# kitcop4.net
KiCad netlist of a schematic drawn in EAGLE
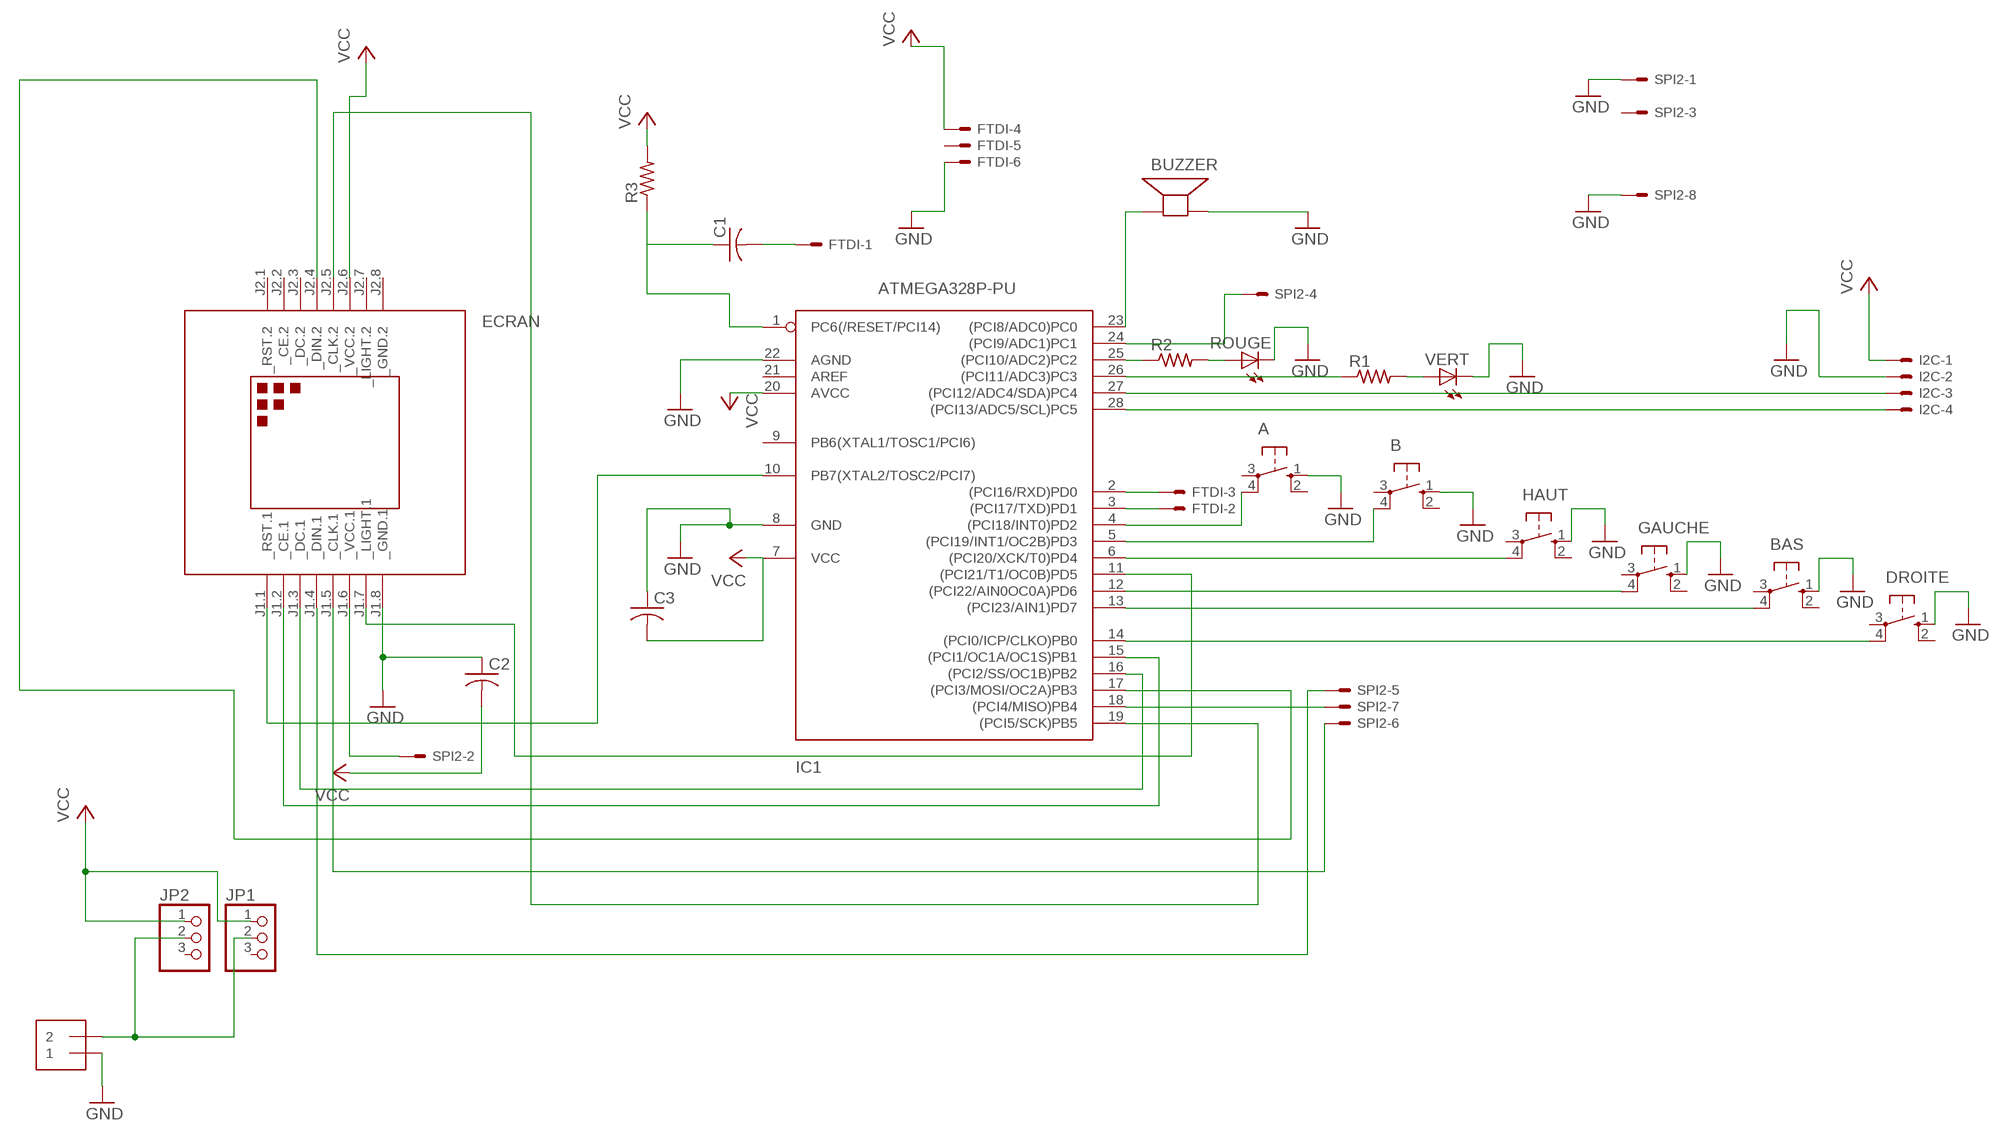
[diagram p0: schematic, sheet 1]

(export (version "E")
  (design (tool "Eeschema 10.0.6"))
  (components
    (comp (ref "A")
      (value "10-XX")
      (footprint "eagle-import:B3F-10XX")
      (fields (field (name "MPN") "B3F-1000"))
      (libsource (lib "eagle-import") (part "10-XX"))
    )
    (comp (ref "B")
      (value "10-XX")
      (footprint "eagle-import:B3F-10XX")
      (fields (field (name "MPN") "B3F-1000"))
      (libsource (lib "eagle-import") (part "10-XX"))
    )
    (comp (ref "BAS")
      (value "10-XX")
      (footprint "eagle-import:B3F-10XX")
      (fields (field (name "MPN") "B3F-1000"))
      (libsource (lib "eagle-import") (part "10-XX"))
    )
    (comp (ref "BUZZER")
      (value "SPEAKER/AL60P")
      (footprint "eagle-import:AL60P")
      (libsource (lib "eagle-import") (part "SPEAKER/AL60P"))
    )
    (comp (ref "C1")
      (value "C-US025-040X050")
      (footprint "eagle-import:C025-040X050")
      (libsource (lib "eagle-import") (part "C-US025-040X050"))
    )
    (comp (ref "C2")
      (value "C-US025-040X050")
      (footprint "eagle-import:C025-040X050")
      (libsource (lib "eagle-import") (part "C-US025-040X050"))
    )
    (comp (ref "C3")
      (value "C-US025-040X050")
      (footprint "eagle-import:C025-040X050")
      (libsource (lib "eagle-import") (part "C-US025-040X050"))
    )
    (comp (ref "DROITE")
      (value "10-XX")
      (footprint "eagle-import:B3F-10XX")
      (fields (field (name "MPN") "B3F-1000"))
      (libsource (lib "eagle-import") (part "10-XX"))
    )
    (comp (ref "ECRAN")
      (value "DISPLAY-NOKIA-3310")
      (footprint "eagle-import:DISPLAY-NOKIA-3310")
      (libsource (lib "eagle-import") (part "DISPLAY-NOKIA-3310"))
    )
    (comp (ref "FTDI")
      (value "22-23-2061")
      (footprint "eagle-import:22-23-2061")
      (fields (field (name "MF") "MOLEX"))
      (libsource (lib "eagle-import") (part "22-23-2061"))
    )
    (comp (ref "GAUCHE")
      (value "10-XX")
      (footprint "eagle-import:B3F-10XX")
      (fields (field (name "MPN") "B3F-1000"))
      (libsource (lib "eagle-import") (part "10-XX"))
    )
    (comp (ref "HAUT")
      (value "10-XX")
      (footprint "eagle-import:B3F-10XX")
      (fields (field (name "MPN") "B3F-1000"))
      (libsource (lib "eagle-import") (part "10-XX"))
    )
    (comp (ref "I2C")
      (value "22-23-2041")
      (footprint "eagle-import:22-23-2041")
      (fields (field (name "MF") "MOLEX"))
      (libsource (lib "eagle-import") (part "22-23-2041"))
    )
    (comp (ref "IC1")
      (value "ATMEGA328P-PU")
      (footprint "eagle-import:DIL28-3")
      (libsource (lib "eagle-import") (part "ATMEGA168PV-10"))
    )
    (comp (ref "J1")
      (value "1X2-3.5MM")
      (footprint "eagle-import:1X2-3.5MM")
      (libsource (lib "eagle-import") (part "1X2-3.5MM"))
    )
    (comp (ref "JP1")
      (value "PINHD-1X3")
      (footprint "eagle-import:1X03")
      (libsource (lib "eagle-import") (part "PINHD-1X3"))
    )
    (comp (ref "JP2")
      (value "PINHD-1X3")
      (footprint "eagle-import:1X03")
      (libsource (lib "eagle-import") (part "PINHD-1X3"))
    )
    (comp (ref "R1")
      (value "R-US_0207/10")
      (footprint "eagle-import:0207_10")
      (libsource (lib "eagle-import") (part "R-US_0207/10"))
    )
    (comp (ref "R2")
      (value "R-US_0207/10")
      (footprint "eagle-import:0207_10")
      (libsource (lib "eagle-import") (part "R-US_0207/10"))
    )
    (comp (ref "R3")
      (value "R-US_0207/10")
      (footprint "eagle-import:0207_10")
      (libsource (lib "eagle-import") (part "R-US_0207/10"))
    )
    (comp (ref "ROUGE")
      (value "LED5MM")
      (footprint "eagle-import:LED5MM")
      (libsource (lib "eagle-import") (part "LED5MM"))
    )
    (comp (ref "SPI2")
      (value "22-23-2081")
      (footprint "eagle-import:22-23-2081")
      (fields (field (name "MF") "MOLEX"))
      (libsource (lib "eagle-import") (part "22-23-2081"))
    )
    (comp (ref "VERT")
      (value "LED5MM")
      (footprint "eagle-import:LED5MM")
      (libsource (lib "eagle-import") (part "LED5MM"))
    )
  )
  (nets
    (net (code "1") (name "/_CE.2") (class "Default")
      (node (ref "ECRAN") (pin "J2.2") (pinfunction "_CE.2_J2.2") (pintype "power_in"))
    )
    (net (code "2") (name "/_RST.2") (class "Default")
      (node (ref "ECRAN") (pin "J2.1") (pinfunction "_RST.2_J2.1") (pintype "power_in"))
    )
    (net (code "3") (name "GND") (class "Default")
      (node (ref "A") (pin "1") (pinfunction "S_1") (pintype "passive"))
      (node (ref "B") (pin "1") (pinfunction "S_1") (pintype "passive"))
      (node (ref "BAS") (pin "1") (pinfunction "S_1") (pintype "passive"))
      (node (ref "BUZZER") (pin "2") (pinfunction "-_2") (pintype "passive"))
      (node (ref "C2") (pin "1") (pinfunction "1_1") (pintype "passive"))
      (node (ref "C3") (pin "1") (pinfunction "1_1") (pintype "passive"))
      (node (ref "DROITE") (pin "1") (pinfunction "S_1") (pintype "passive"))
      (node (ref "ECRAN") (pin "J1.8") (pinfunction "_GND.1_J1.8") (pintype "input"))
      (node (ref "FTDI") (pin "6") (pinfunction "S_6") (pintype "passive"))
      (node (ref "GAUCHE") (pin "1") (pinfunction "S_1") (pintype "passive"))
      (node (ref "HAUT") (pin "1") (pinfunction "S_1") (pintype "passive"))
      (node (ref "I2C") (pin "2") (pinfunction "S_2") (pintype "passive"))
      (node (ref "IC1") (pin "22") (pinfunction "AGND_22") (pintype "bidirectional"))
      (node (ref "IC1") (pin "8") (pinfunction "GND_8") (pintype "bidirectional"))
      (node (ref "J1") (pin "1") (pinfunction "1_1") (pintype "passive"))
      (node (ref "ROUGE") (pin "K") (pinfunction "C_K") (pintype "passive"))
      (node (ref "SPI2") (pin "1") (pinfunction "S_1") (pintype "passive"))
      (node (ref "SPI2") (pin "8") (pinfunction "S_8") (pintype "passive"))
      (node (ref "VERT") (pin "K") (pinfunction "C_K") (pintype "passive"))
    )
    (net (code "4") (name "Net-(A-P1)") (class "Default")
      (node (ref "A") (pin "4") (pinfunction "P1_4") (pintype "passive"))
      (node (ref "IC1") (pin "4") (pinfunction "(PCI18/INT0)PD2_4") (pintype "bidirectional"))
    )
    (net (code "5") (name "Net-(B-P1)") (class "Default")
      (node (ref "B") (pin "4") (pinfunction "P1_4") (pintype "passive"))
      (node (ref "IC1") (pin "5") (pinfunction "(PCI19/INT1/OC2B)PD3_5") (pintype "bidirectional"))
    )
    (net (code "6") (name "Net-(BAS-P1)") (class "Default")
      (node (ref "BAS") (pin "4") (pinfunction "P1_4") (pintype "passive"))
      (node (ref "IC1") (pin "13") (pinfunction "(PCI23/AIN1)PD7_13") (pintype "bidirectional"))
    )
    (net (code "7") (name "Net-(BUZZER-+)") (class "Default")
      (node (ref "BUZZER") (pin "1") (pinfunction "+_1") (pintype "passive"))
      (node (ref "IC1") (pin "23") (pinfunction "(PCI8/ADC0)PC0_23") (pintype "bidirectional"))
    )
    (net (code "8") (name "Net-(DROITE-P1)") (class "Default")
      (node (ref "DROITE") (pin "4") (pinfunction "P1_4") (pintype "passive"))
      (node (ref "IC1") (pin "14") (pinfunction "(PCI0/ICP/CLKO)PB0_14") (pintype "bidirectional"))
    )
    (net (code "9") (name "Net-(ECRAN-_CE.1)") (class "Default")
      (node (ref "ECRAN") (pin "J1.2") (pinfunction "_CE.1_J1.2") (pintype "power_in"))
      (node (ref "IC1") (pin "15") (pinfunction "(PCI1/OC1A/OC1S)PB1_15") (pintype "bidirectional"))
    )
    (net (code "10") (name "Net-(ECRAN-_CLK.1)") (class "Default")
      (node (ref "ECRAN") (pin "J1.5") (pinfunction "_CLK.1_J1.5") (pintype "bidirectional"))
      (node (ref "SPI2") (pin "6") (pinfunction "S_6") (pintype "passive"))
    )
    (net (code "11") (name "Net-(ECRAN-_CLK.2)") (class "Default")
      (node (ref "ECRAN") (pin "J2.5") (pinfunction "_CLK.2_J2.5") (pintype "bidirectional"))
      (node (ref "IC1") (pin "19") (pinfunction "(PCI5/SCK)PB5_19") (pintype "bidirectional"))
    )
    (net (code "12") (name "Net-(ECRAN-_DC.1)") (class "Default")
      (node (ref "ECRAN") (pin "J1.3") (pinfunction "_DC.1_J1.3") (pintype "bidirectional"))
      (node (ref "IC1") (pin "16") (pinfunction "(PCI2/SS/OC1B)PB2_16") (pintype "bidirectional"))
    )
    (net (code "13") (name "Net-(ECRAN-_DIN.1)") (class "Default")
      (node (ref "ECRAN") (pin "J1.4") (pinfunction "_DIN.1_J1.4") (pintype "bidirectional"))
      (node (ref "SPI2") (pin "5") (pinfunction "S_5") (pintype "passive"))
    )
    (net (code "14") (name "Net-(ECRAN-_DIN.2)") (class "Default")
      (node (ref "ECRAN") (pin "J2.4") (pinfunction "_DIN.2_J2.4") (pintype "bidirectional"))
      (node (ref "IC1") (pin "17") (pinfunction "(PCI3/MOSI/OC2A)PB3_17") (pintype "bidirectional"))
    )
    (net (code "15") (name "Net-(ECRAN-_LIGHT.1)") (class "Default")
      (node (ref "ECRAN") (pin "J1.7") (pinfunction "_LIGHT.1_J1.7") (pintype "bidirectional"))
      (node (ref "IC1") (pin "11") (pinfunction "(PCI21/T1/OC0B)PD5_11") (pintype "bidirectional"))
    )
    (net (code "16") (name "Net-(ECRAN-_RST.1)") (class "Default")
      (node (ref "ECRAN") (pin "J1.1") (pinfunction "_RST.1_J1.1") (pintype "power_in"))
      (node (ref "IC1") (pin "10") (pinfunction "PB7(XTAL2/TOSC2/PCI7)_10") (pintype "bidirectional"))
    )
    (net (code "17") (name "Net-(ECRAN-_VCC.1)") (class "Default")
      (node (ref "ECRAN") (pin "J1.6") (pinfunction "_VCC.1_J1.6") (pintype "bidirectional"))
      (node (ref "SPI2") (pin "2") (pinfunction "S_2") (pintype "passive"))
    )
    (net (code "18") (name "Net-(FTDIA-S)") (class "Default")
      (node (ref "C1") (pin "2") (pinfunction "2_2") (pintype "passive"))
      (node (ref "FTDI") (pin "1") (pinfunction "S_1") (pintype "passive"))
    )
    (net (code "19") (name "Net-(FTDIB-S)") (class "Default")
      (node (ref "FTDI") (pin "2") (pinfunction "S_2") (pintype "passive"))
      (node (ref "IC1") (pin "3") (pinfunction "(PCI17/TXD)PD1_3") (pintype "bidirectional"))
    )
    (net (code "20") (name "Net-(FTDIC-S)") (class "Default")
      (node (ref "FTDI") (pin "3") (pinfunction "S_3") (pintype "passive"))
      (node (ref "IC1") (pin "2") (pinfunction "(PCI16/RXD)PD0_2") (pintype "bidirectional"))
    )
    (net (code "21") (name "Net-(GAUCHE-P1)") (class "Default")
      (node (ref "GAUCHE") (pin "4") (pinfunction "P1_4") (pintype "passive"))
      (node (ref "IC1") (pin "12") (pinfunction "(PCI22/AIN0OC0A)PD6_12") (pintype "bidirectional"))
    )
    (net (code "22") (name "Net-(HAUT-P1)") (class "Default")
      (node (ref "HAUT") (pin "4") (pinfunction "P1_4") (pintype "passive"))
      (node (ref "IC1") (pin "6") (pinfunction "(PCI20/XCK/T0)PD4_6") (pintype "bidirectional"))
    )
    (net (code "23") (name "Net-(I2CC-S)") (class "Default")
      (node (ref "I2C") (pin "3") (pinfunction "S_3") (pintype "passive"))
      (node (ref "IC1") (pin "27") (pinfunction "(PCI12/ADC4/SDA)PC4_27") (pintype "bidirectional"))
    )
    (net (code "24") (name "Net-(I2CD-S)") (class "Default")
      (node (ref "I2C") (pin "4") (pinfunction "S_4") (pintype "passive"))
      (node (ref "IC1") (pin "28") (pinfunction "(PCI13/ADC5/SCL)PC5_28") (pintype "bidirectional"))
    )
    (net (code "25") (name "Net-(IC1-(PCI4{slash}MISO)PB4)") (class "Default")
      (node (ref "IC1") (pin "18") (pinfunction "(PCI4/MISO)PB4_18") (pintype "bidirectional"))
      (node (ref "SPI2") (pin "7") (pinfunction "S_7") (pintype "passive"))
    )
    (net (code "26") (name "Net-(IC1-(PCI9{slash}ADC1)PC1)") (class "Default")
      (node (ref "IC1") (pin "24") (pinfunction "(PCI9/ADC1)PC1_24") (pintype "bidirectional"))
      (node (ref "SPI2") (pin "4") (pinfunction "S_4") (pintype "passive"))
    )
    (net (code "27") (name "Net-(IC1-(PCI10{slash}ADC2)PC2)") (class "Default")
      (node (ref "IC1") (pin "25") (pinfunction "(PCI10/ADC2)PC2_25") (pintype "bidirectional"))
      (node (ref "R2") (pin "1") (pinfunction "1_1") (pintype "passive"))
    )
    (net (code "28") (name "Net-(IC1-(PCI11{slash}ADC3)PC3)") (class "Default")
      (node (ref "IC1") (pin "26") (pinfunction "(PCI11/ADC3)PC3_26") (pintype "bidirectional"))
      (node (ref "R1") (pin "1") (pinfunction "1_1") (pintype "passive"))
    )
    (net (code "29") (name "Net-(IC1-PC6({slash}RESET{slash}PCI14))") (class "Default")
      (node (ref "C1") (pin "1") (pinfunction "1_1") (pintype "passive"))
      (node (ref "IC1") (pin "1") (pinfunction "PC6(/RESET/PCI14)_1") (pintype "bidirectional"))
      (node (ref "R3") (pin "1") (pinfunction "1_1") (pintype "passive"))
    )
    (net (code "30") (name "Net-(J1-Pad2)") (class "Default")
      (node (ref "J1") (pin "2") (pinfunction "2_2") (pintype "passive"))
      (node (ref "JP1") (pin "2") (pinfunction "2_2") (pintype "passive"))
      (node (ref "JP2") (pin "2") (pinfunction "2_2") (pintype "passive"))
    )
    (net (code "31") (name "Net-(R1-Pad2)") (class "Default")
      (node (ref "R1") (pin "2") (pinfunction "2_2") (pintype "passive"))
      (node (ref "VERT") (pin "A") (pinfunction "A_A") (pintype "passive"))
    )
    (net (code "32") (name "Net-(R2-Pad2)") (class "Default")
      (node (ref "R2") (pin "2") (pinfunction "2_2") (pintype "passive"))
      (node (ref "ROUGE") (pin "A") (pinfunction "A_A") (pintype "passive"))
    )
    (net (code "33") (name "VCC") (class "Default")
      (node (ref "C2") (pin "2") (pinfunction "2_2") (pintype "passive"))
      (node (ref "C3") (pin "2") (pinfunction "2_2") (pintype "passive"))
      (node (ref "ECRAN") (pin "J2.6") (pinfunction "_VCC.2_J2.6") (pintype "bidirectional"))
      (node (ref "FTDI") (pin "4") (pinfunction "S_4") (pintype "passive"))
      (node (ref "I2C") (pin "1") (pinfunction "S_1") (pintype "passive"))
      (node (ref "IC1") (pin "20") (pinfunction "AVCC_20") (pintype "bidirectional"))
      (node (ref "IC1") (pin "7") (pinfunction "VCC_7") (pintype "bidirectional"))
      (node (ref "JP1") (pin "1") (pinfunction "1_1") (pintype "passive"))
      (node (ref "JP2") (pin "1") (pinfunction "1_1") (pintype "passive"))
      (node (ref "R3") (pin "2") (pinfunction "2_2") (pintype "passive"))
    )
    (net (code "34") (name "unconnected-(A-P-Pad3)") (class "Default")
      (node (ref "A") (pin "3") (pinfunction "P_3") (pintype "passive"))
    )
    (net (code "35") (name "unconnected-(A-S1-Pad2)") (class "Default")
      (node (ref "A") (pin "2") (pinfunction "S1_2") (pintype "passive"))
    )
    (net (code "36") (name "unconnected-(B-P-Pad3)") (class "Default")
      (node (ref "B") (pin "3") (pinfunction "P_3") (pintype "passive"))
    )
    (net (code "37") (name "unconnected-(B-S1-Pad2)") (class "Default")
      (node (ref "B") (pin "2") (pinfunction "S1_2") (pintype "passive"))
    )
    (net (code "38") (name "unconnected-(BAS-P-Pad3)") (class "Default")
      (node (ref "BAS") (pin "3") (pinfunction "P_3") (pintype "passive"))
    )
    (net (code "39") (name "unconnected-(BAS-S1-Pad2)") (class "Default")
      (node (ref "BAS") (pin "2") (pinfunction "S1_2") (pintype "passive"))
    )
    (net (code "40") (name "unconnected-(DROITE-P-Pad3)") (class "Default")
      (node (ref "DROITE") (pin "3") (pinfunction "P_3") (pintype "passive"))
    )
    (net (code "41") (name "unconnected-(DROITE-S1-Pad2)") (class "Default")
      (node (ref "DROITE") (pin "2") (pinfunction "S1_2") (pintype "passive"))
    )
    (net (code "42") (name "unconnected-(ECRAN-_DC.2-PadJ2.3)") (class "Default")
      (node (ref "ECRAN") (pin "J2.3") (pinfunction "_DC.2_J2.3") (pintype "bidirectional"))
    )
    (net (code "43") (name "unconnected-(ECRAN-_GND.2-PadJ2.8)") (class "Default")
      (node (ref "ECRAN") (pin "J2.8") (pinfunction "_GND.2_J2.8") (pintype "input"))
    )
    (net (code "44") (name "unconnected-(ECRAN-_LIGHT.2-PadJ2.7)") (class "Default")
      (node (ref "ECRAN") (pin "J2.7") (pinfunction "_LIGHT.2_J2.7") (pintype "bidirectional"))
    )
    (net (code "45") (name "unconnected-(FTDIE-S-Pad5)") (class "Default")
      (node (ref "FTDI") (pin "5") (pinfunction "S_5") (pintype "passive"))
    )
    (net (code "46") (name "unconnected-(GAUCHE-P-Pad3)") (class "Default")
      (node (ref "GAUCHE") (pin "3") (pinfunction "P_3") (pintype "passive"))
    )
    (net (code "47") (name "unconnected-(GAUCHE-S1-Pad2)") (class "Default")
      (node (ref "GAUCHE") (pin "2") (pinfunction "S1_2") (pintype "passive"))
    )
    (net (code "48") (name "unconnected-(HAUT-P-Pad3)") (class "Default")
      (node (ref "HAUT") (pin "3") (pinfunction "P_3") (pintype "passive"))
    )
    (net (code "49") (name "unconnected-(HAUT-S1-Pad2)") (class "Default")
      (node (ref "HAUT") (pin "2") (pinfunction "S1_2") (pintype "passive"))
    )
    (net (code "50") (name "unconnected-(IC1-AREF-Pad21)") (class "Default")
      (node (ref "IC1") (pin "21") (pinfunction "AREF_21") (pintype "bidirectional"))
    )
    (net (code "51") (name "unconnected-(IC1-PB6(XTAL1{slash}TOSC1{slash}PCI6)-Pad9)") (class "Default")
      (node (ref "IC1") (pin "9") (pinfunction "PB6(XTAL1/TOSC1/PCI6)_9") (pintype "bidirectional"))
    )
    (net (code "52") (name "unconnected-(JP1-Pad3)") (class "Default")
      (node (ref "JP1") (pin "3") (pinfunction "3_3") (pintype "passive"))
    )
    (net (code "53") (name "unconnected-(JP2-Pad3)") (class "Default")
      (node (ref "JP2") (pin "3") (pinfunction "3_3") (pintype "passive"))
    )
    (net (code "54") (name "unconnected-(SPI2C-S-Pad3)") (class "Default")
      (node (ref "SPI2") (pin "3") (pinfunction "S_3") (pintype "passive"))
    )
  )
)
